# HumFlex1.net
KiCad netlist of a schematic drawn in Altium Designer
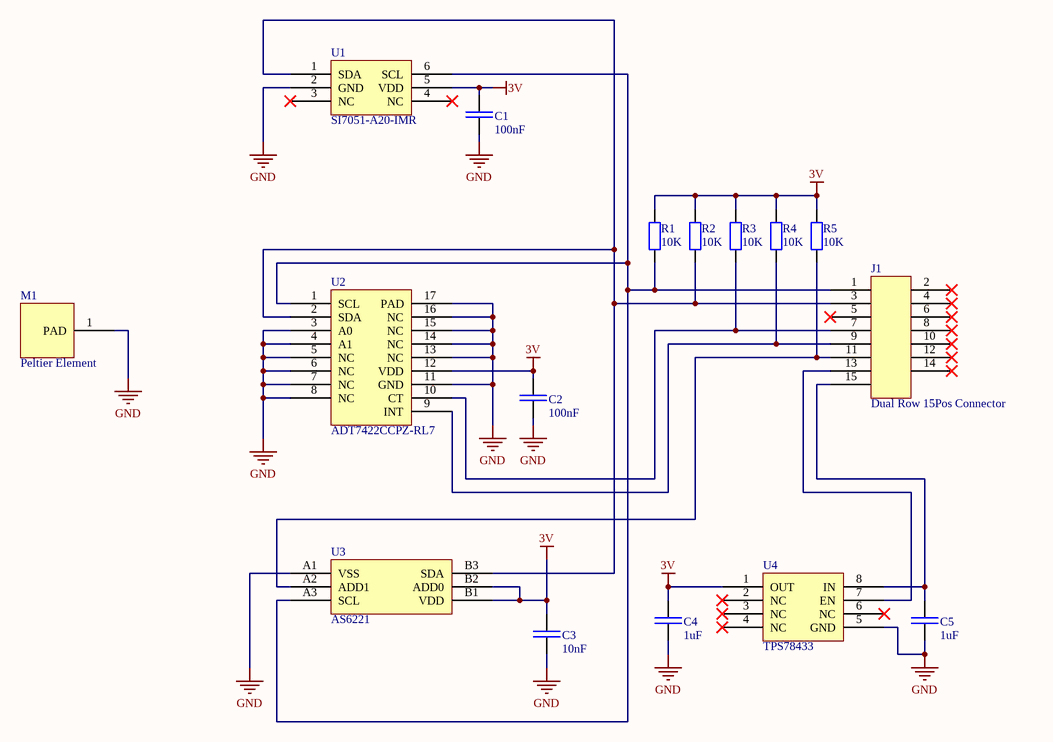
[diagram p0: HumFlex1.SchDoc]

(export (version "E")
  (design (tool "Eeschema 10.0.6"))
  (components
    (comp (ref "C1")
      (value "100nF")
      (footprint "CAP_SM0603_YAGEOCC2_N")
      (description "CAP 100nF SM0603 X7R 50V YAGEO CC2")
      (fields
        (field (name "MANUFACTURER") "Yageo")
        (field (name "MANUFACTURER PART NUMBER") "CC0603KRX7R9BB104")
      )
      (libsource (lib "symbols") (part "CC0603KRX7R9BB104"))
    )
    (comp (ref "C2")
      (value "100nF")
      (footprint "CAP_SM0603_YAGEOCC2_N")
      (description "CAP 100nF SM0603 X7R 50V YAGEO CC2")
      (fields
        (field (name "MANUFACTURER") "Yageo")
        (field (name "MANUFACTURER PART NUMBER") "CC0603KRX7R9BB104")
      )
      (libsource (lib "symbols") (part "CC0603KRX7R9BB104"))
    )
    (comp (ref "C3")
      (value "10nF")
      (footprint "CAP_SM0402_YAGEOCC2_N")
      (description "CAP 10nF SM0402 X7R 50V YAGEO CC2")
      (fields
        (field (name "MANUFACTURER") "Yageo")
        (field (name "MANUFACTURER PART NUMBER") "CC0603KRX7R9BB103")
      )
      (libsource (lib "symbols") (part "CC0402KRX7R9BB103"))
    )
    (comp (ref "C4")
      (value "1uF")
      (footprint "CAP_SM0805_YAGEOCC2_N")
      (description "CAP 1uF SM0805 X7R 25V YAGEO CC2")
      (fields
        (field (name "MANUFACTURER") "Yageo")
        (field (name "MANUFACTURER PART NUMBER") "CC0805KKX7R8BB105")
      )
      (libsource (lib "symbols") (part "CC0805KKX7R8BB105"))
    )
    (comp (ref "C5")
      (value "1uF")
      (footprint "CAP_SM0805_YAGEOCC2_N")
      (description "CAP 1uF SM0805 X7R 25V YAGEO CC2")
      (fields
        (field (name "MANUFACTURER") "Yageo")
        (field (name "MANUFACTURER PART NUMBER") "CC0805KKX7R8BB105")
      )
      (libsource (lib "symbols") (part "CC0805KKX7R8BB105"))
    )
    (comp (ref "J1")
      (value "Dual Row 15Pos Connector")
      (footprint "AYF331535_FPC")
      (libsource (lib "symbols") (part "Connector_15_DualRow"))
    )
    (comp (ref "M1")
      (value "Peltier Element")
      (footprint "PeltierElement")
      (description "Peltier element 40mm x 40mm")
      (libsource (lib "symbols") (part "PeltierElement"))
    )
    (comp (ref "R1")
      (value "10K")
      (footprint "RES_SM0603_YAGEORC_N")
      (description "RES 10K SM0603 YAGEO RC_L")
      (fields
        (field (name "MANUFACTURER") "Yageo")
        (field (name "MANUFACTURER PART NUMBER") "RC0603FR-0710KL")
      )
      (libsource (lib "symbols") (part "RC0603FR-0710KL"))
    )
    (comp (ref "R2")
      (value "10K")
      (footprint "RES_SM0603_YAGEORC_N")
      (description "RES 10K SM0603 YAGEO RC_L")
      (fields
        (field (name "MANUFACTURER") "Yageo")
        (field (name "MANUFACTURER PART NUMBER") "RC0603FR-0710KL")
      )
      (libsource (lib "symbols") (part "RC0603FR-0710KL"))
    )
    (comp (ref "R3")
      (value "10K")
      (footprint "RES_SM0603_YAGEORC_N")
      (description "RES 10K SM0603 YAGEO RC_L")
      (fields
        (field (name "MANUFACTURER") "Yageo")
        (field (name "MANUFACTURER PART NUMBER") "RC0603FR-0710KL")
      )
      (libsource (lib "symbols") (part "RC0603FR-0710KL"))
    )
    (comp (ref "R4")
      (value "10K")
      (footprint "RES_SM0603_YAGEORC_N")
      (description "RES 10K SM0603 YAGEO RC_L")
      (fields
        (field (name "MANUFACTURER") "Yageo")
        (field (name "MANUFACTURER PART NUMBER") "RC0603FR-0710KL")
      )
      (libsource (lib "symbols") (part "RC0603FR-0710KL"))
    )
    (comp (ref "R5")
      (value "10K")
      (footprint "RES_SM0603_YAGEORC_N")
      (description "RES 10K SM0603 YAGEO RC_L")
      (fields
        (field (name "MANUFACTURER") "Yageo")
        (field (name "MANUFACTURER PART NUMBER") "RC0603FR-0710KL")
      )
      (libsource (lib "symbols") (part "RC0603FR-0710KL"))
    )
    (comp (ref "U1")
      (value "SI7051-A20-IMR")
      (footprint "SI7050/1/2/3/4/5")
      (description "Si7051-A20 Temperature Sensor ±0.1°C maximum accuracy, Digital I2C, -40°C ~ 125°C 14b 6-DFN (3x3)")
      (libsource (lib "symbols") (part "SI7051-A20-IMR"))
    )
    (comp (ref "U2")
      (value "ADT7422CCPZ-RL7")
      (footprint "ADT7422_QFN")
      (libsource (lib "symbols") (part "ADT7422CCPZ-RL7"))
    )
    (comp (ref "U3")
      (value "AS6221")
      (footprint "AS6221_BGA")
      (description "AS6221 Temperature Sensor Digital -40°C ~ 125°C 16b 6-WLCSP (1.5x1.03)")
      (libsource (lib "symbols") (part "AS6221-AWLT-S"))
    )
    (comp (ref "U4")
      (value "TPS78433")
      (footprint "TPS784xxxQDRBRQ1_SON")
      (libsource (lib "symbols") (part "TPS78433QWDRBRQ1"))
    )
  )
  (nets
    (net (code "1") (name "3V") (class "Default")
      (node (ref "C1") (pin "2") (pintype "passive"))
      (node (ref "C2") (pin "2") (pintype "passive"))
      (node (ref "C3") (pin "1") (pintype "passive"))
      (node (ref "C4") (pin "2") (pintype "passive"))
      (node (ref "R1") (pin "2") (pintype "passive"))
      (node (ref "R2") (pin "2") (pintype "passive"))
      (node (ref "R3") (pin "2") (pintype "passive"))
      (node (ref "R4") (pin "2") (pintype "passive"))
      (node (ref "R5") (pin "2") (pintype "passive"))
      (node (ref "U1") (pin "5") (pinfunction "VDD_5") (pintype "passive"))
      (node (ref "U2") (pin "12") (pinfunction "VDD_12") (pintype "passive"))
      (node (ref "U3") (pin "B1") (pinfunction "VDD_B1") (pintype "passive"))
      (node (ref "U3") (pin "B2") (pinfunction "ADD0_B2") (pintype "passive"))
      (node (ref "U4") (pin "1") (pinfunction "OUT_1") (pintype "passive"))
    )
    (net (code "2") (name "GND") (class "Default")
      (node (ref "C1") (pin "1") (pintype "passive"))
      (node (ref "C2") (pin "1") (pintype "passive"))
      (node (ref "C3") (pin "2") (pintype "passive"))
      (node (ref "C4") (pin "1") (pintype "passive"))
      (node (ref "C5") (pin "1") (pintype "passive"))
      (node (ref "M1") (pin "1") (pinfunction "PAD_1") (pintype "passive"))
      (node (ref "U1") (pin "2") (pinfunction "GND_2") (pintype "passive"))
      (node (ref "U2") (pin "11") (pinfunction "GND_11") (pintype "passive"))
      (node (ref "U2") (pin "13") (pinfunction "NC_13") (pintype "passive"))
      (node (ref "U2") (pin "14") (pinfunction "NC_14") (pintype "passive"))
      (node (ref "U2") (pin "15") (pinfunction "NC_15") (pintype "passive"))
      (node (ref "U2") (pin "16") (pinfunction "NC_16") (pintype "passive"))
      (node (ref "U2") (pin "17") (pinfunction "PAD_17") (pintype "passive"))
      (node (ref "U2") (pin "3") (pinfunction "A0_3") (pintype "passive"))
      (node (ref "U2") (pin "4") (pinfunction "A1_4") (pintype "passive"))
      (node (ref "U2") (pin "5") (pinfunction "NC_5") (pintype "passive"))
      (node (ref "U2") (pin "6") (pinfunction "NC_6") (pintype "passive"))
      (node (ref "U2") (pin "7") (pinfunction "NC_7") (pintype "passive"))
      (node (ref "U2") (pin "8") (pinfunction "NC_8") (pintype "passive"))
      (node (ref "U3") (pin "A1") (pinfunction "VSS_A1") (pintype "passive"))
      (node (ref "U4") (pin "5") (pinfunction "GND_5") (pintype "passive"))
    )
    (net (code "3") (name "Net-(U1-SCL)") (class "Default")
      (node (ref "J1") (pin "1") (pintype "passive"))
      (node (ref "R1") (pin "1") (pintype "passive"))
      (node (ref "U1") (pin "6") (pinfunction "SCL_6") (pintype "passive"))
      (node (ref "U2") (pin "1") (pinfunction "SCL_1") (pintype "passive"))
      (node (ref "U3") (pin "A3") (pinfunction "SCL_A3") (pintype "passive"))
    )
    (net (code "4") (name "Net-(U1-SDA)") (class "Default")
      (node (ref "J1") (pin "3") (pintype "passive"))
      (node (ref "R2") (pin "1") (pintype "passive"))
      (node (ref "U1") (pin "1") (pinfunction "SDA_1") (pintype "passive"))
      (node (ref "U2") (pin "2") (pinfunction "SDA_2") (pintype "passive"))
      (node (ref "U3") (pin "B3") (pinfunction "SDA_B3") (pintype "passive"))
    )
    (net (code "5") (name "Net-(U2-CT)") (class "Default")
      (node (ref "J1") (pin "7") (pintype "passive"))
      (node (ref "R3") (pin "1") (pintype "passive"))
      (node (ref "U2") (pin "10") (pinfunction "CT_10") (pintype "passive"))
    )
    (net (code "6") (name "Net-(U2-INT)") (class "Default")
      (node (ref "J1") (pin "9") (pintype "passive"))
      (node (ref "R4") (pin "1") (pintype "passive"))
      (node (ref "U2") (pin "9") (pinfunction "INT_9") (pintype "passive"))
    )
    (net (code "7") (name "Net-(U3-ADD1)") (class "Default")
      (node (ref "J1") (pin "11") (pintype "passive"))
      (node (ref "R5") (pin "1") (pintype "passive"))
      (node (ref "U3") (pin "A2") (pinfunction "ADD1_A2") (pintype "passive"))
    )
    (net (code "8") (name "Net-(U4-EN)") (class "Default")
      (node (ref "J1") (pin "13") (pintype "passive"))
      (node (ref "U4") (pin "7") (pinfunction "EN_7") (pintype "passive"))
    )
    (net (code "9") (name "Net-(U4-IN)") (class "Default")
      (node (ref "C5") (pin "2") (pintype "passive"))
      (node (ref "J1") (pin "15") (pintype "passive"))
      (node (ref "U4") (pin "8") (pinfunction "IN_8") (pintype "passive"))
    )
    (net (code "10") (name "unconnected-(J1-Pad2)") (class "Default")
      (node (ref "J1") (pin "2") (pintype "passive+no_connect"))
    )
    (net (code "11") (name "unconnected-(J1-Pad4)") (class "Default")
      (node (ref "J1") (pin "4") (pintype "passive+no_connect"))
    )
    (net (code "12") (name "unconnected-(J1-Pad5)") (class "Default")
      (node (ref "J1") (pin "5") (pintype "passive+no_connect"))
    )
    (net (code "13") (name "unconnected-(J1-Pad6)") (class "Default")
      (node (ref "J1") (pin "6") (pintype "passive+no_connect"))
    )
    (net (code "14") (name "unconnected-(J1-Pad8)") (class "Default")
      (node (ref "J1") (pin "8") (pintype "passive+no_connect"))
    )
    (net (code "15") (name "unconnected-(J1-Pad10)") (class "Default")
      (node (ref "J1") (pin "10") (pintype "passive+no_connect"))
    )
    (net (code "16") (name "unconnected-(J1-Pad12)") (class "Default")
      (node (ref "J1") (pin "12") (pintype "passive+no_connect"))
    )
    (net (code "17") (name "unconnected-(J1-Pad14)") (class "Default")
      (node (ref "J1") (pin "14") (pintype "passive+no_connect"))
    )
    (net (code "18") (name "unconnected-(U1-NC-Pad3)") (class "Default")
      (node (ref "U1") (pin "3") (pinfunction "NC_3") (pintype "passive+no_connect"))
    )
    (net (code "19") (name "unconnected-(U1-NC-Pad4)") (class "Default")
      (node (ref "U1") (pin "4") (pinfunction "NC_4") (pintype "passive+no_connect"))
    )
    (net (code "20") (name "unconnected-(U4-NC-Pad2)") (class "Default")
      (node (ref "U4") (pin "2") (pinfunction "NC_2") (pintype "passive+no_connect"))
    )
    (net (code "21") (name "unconnected-(U4-NC-Pad3)") (class "Default")
      (node (ref "U4") (pin "3") (pinfunction "NC_3") (pintype "passive+no_connect"))
    )
    (net (code "22") (name "unconnected-(U4-NC-Pad4)") (class "Default")
      (node (ref "U4") (pin "4") (pinfunction "NC_4") (pintype "passive+no_connect"))
    )
    (net (code "23") (name "unconnected-(U4-NC-Pad6)") (class "Default")
      (node (ref "U4") (pin "6") (pinfunction "NC_6") (pintype "passive+no_connect"))
    )
  )
)
